# Now_Communicator_Apr_17_2026.net
KiCad netlist of a schematic drawn in EasyEDA
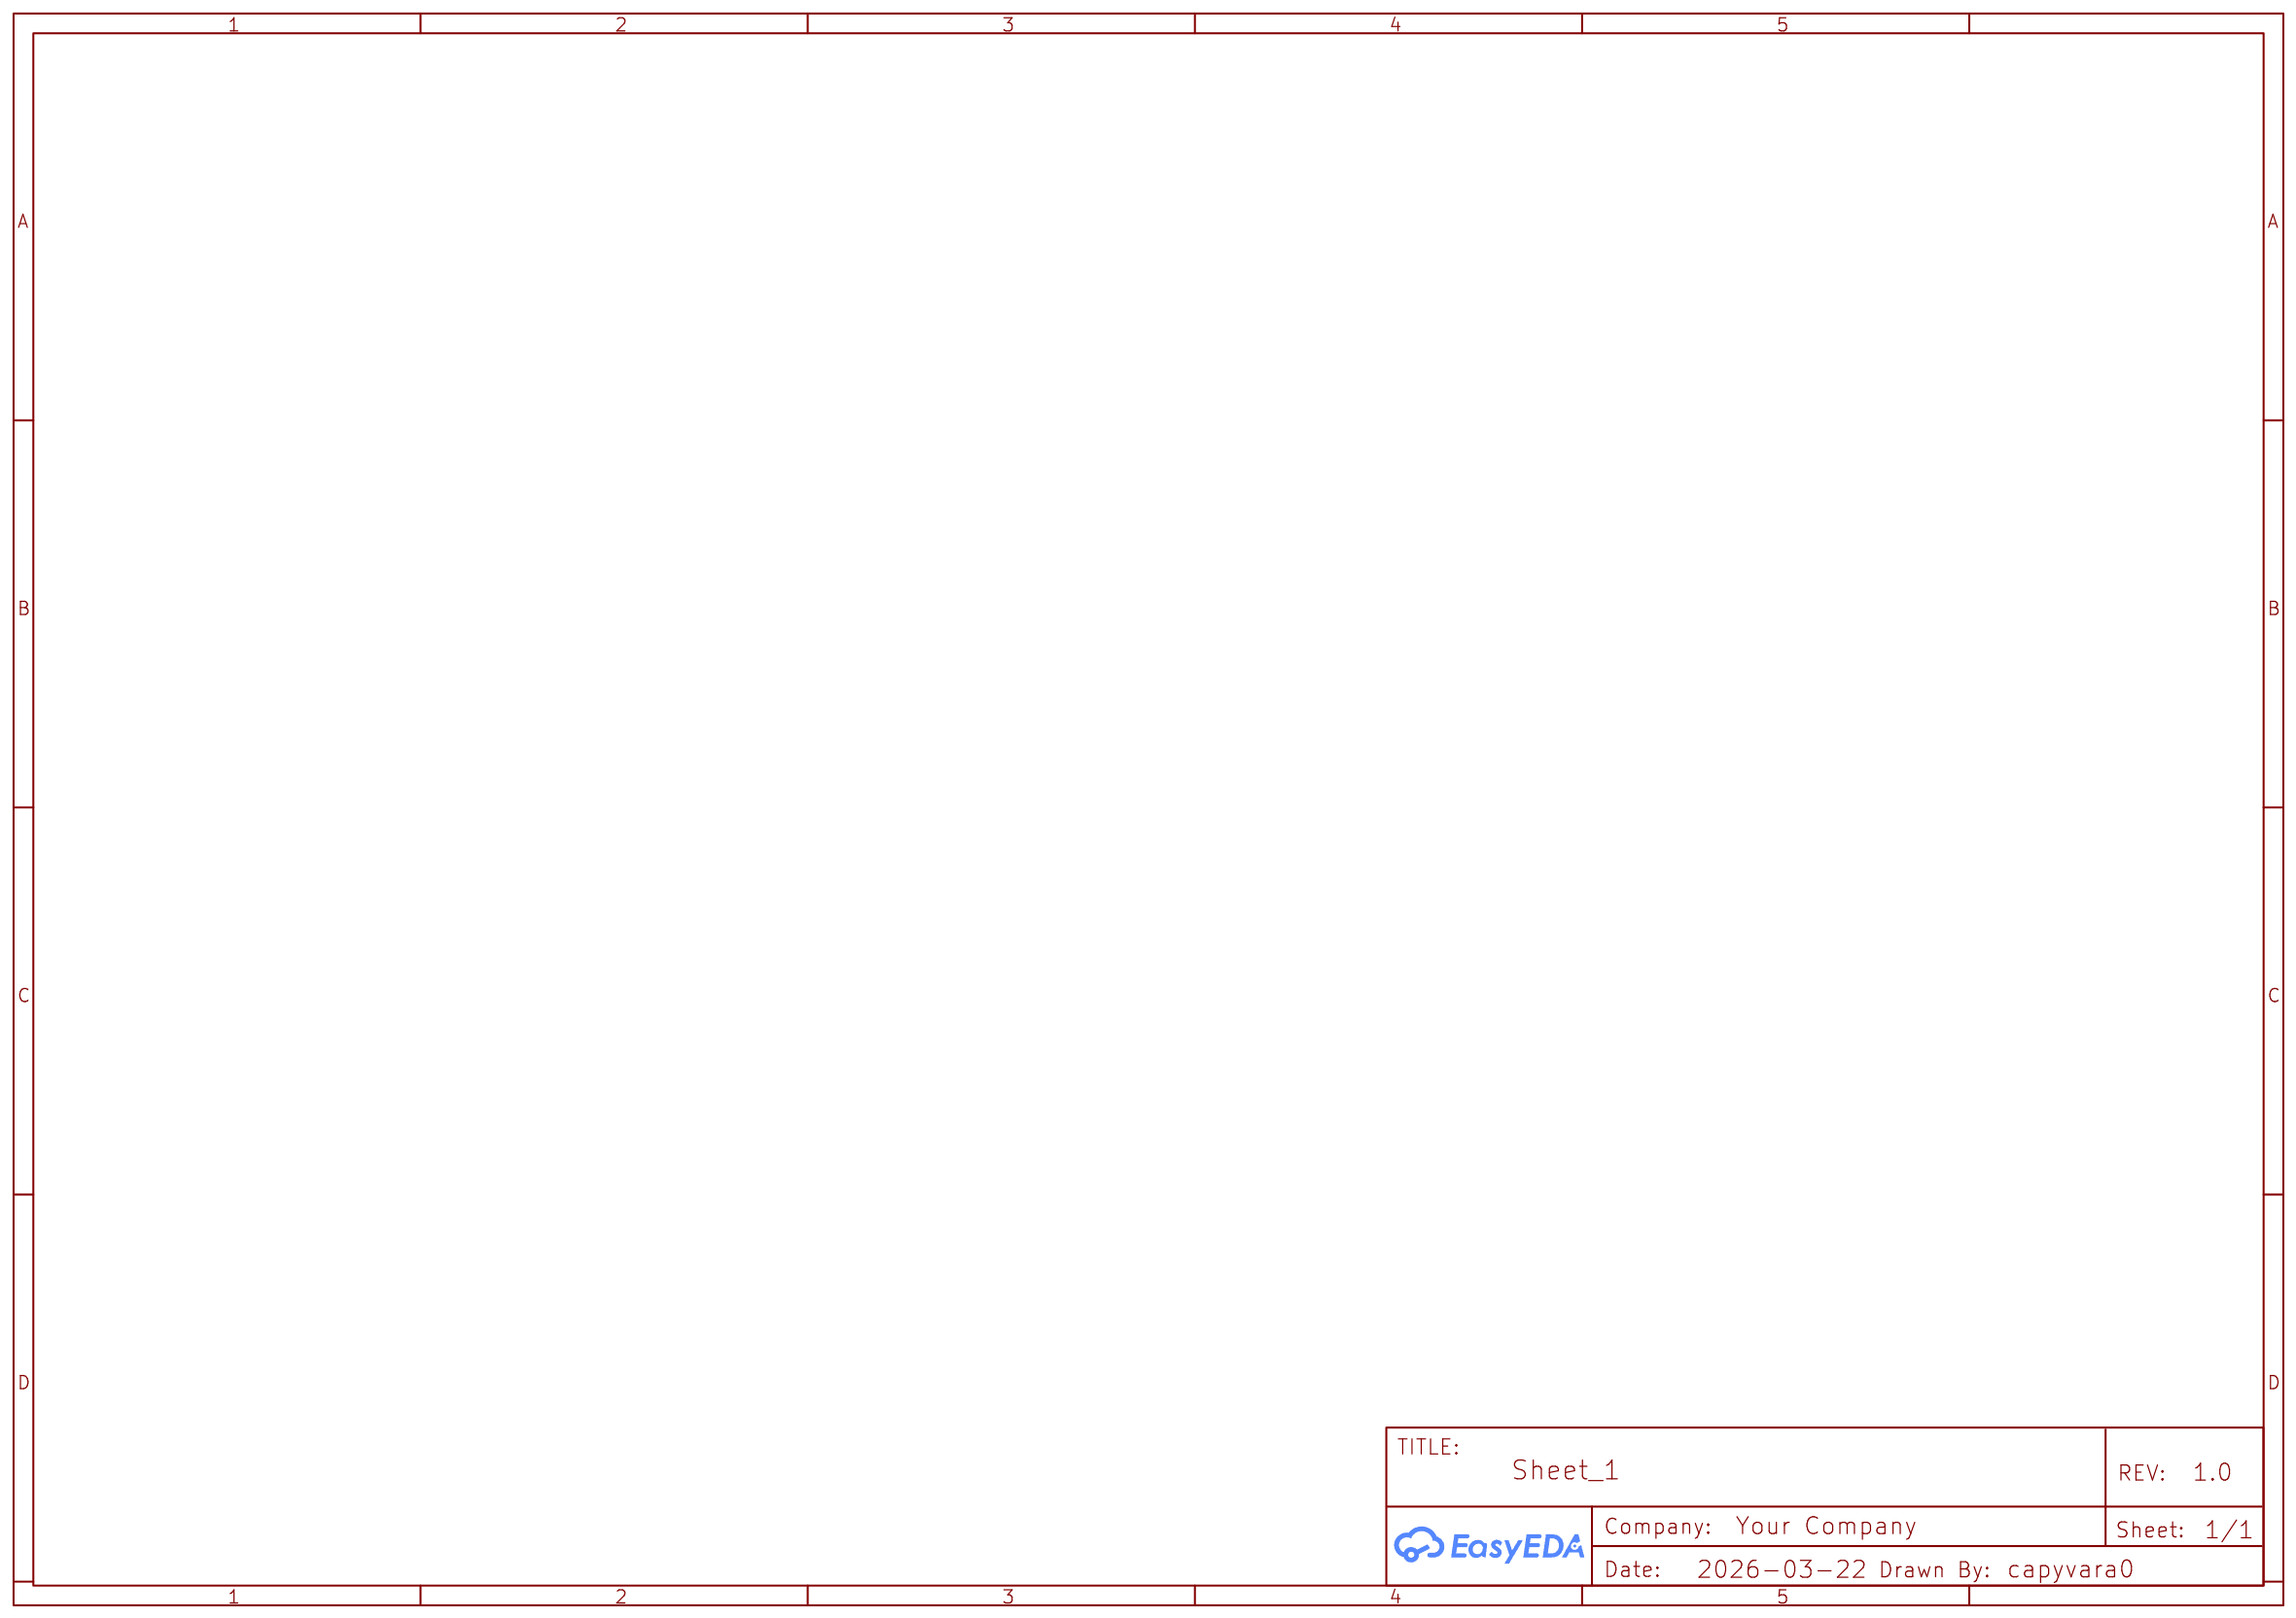
[diagram p0: Sheet_1]
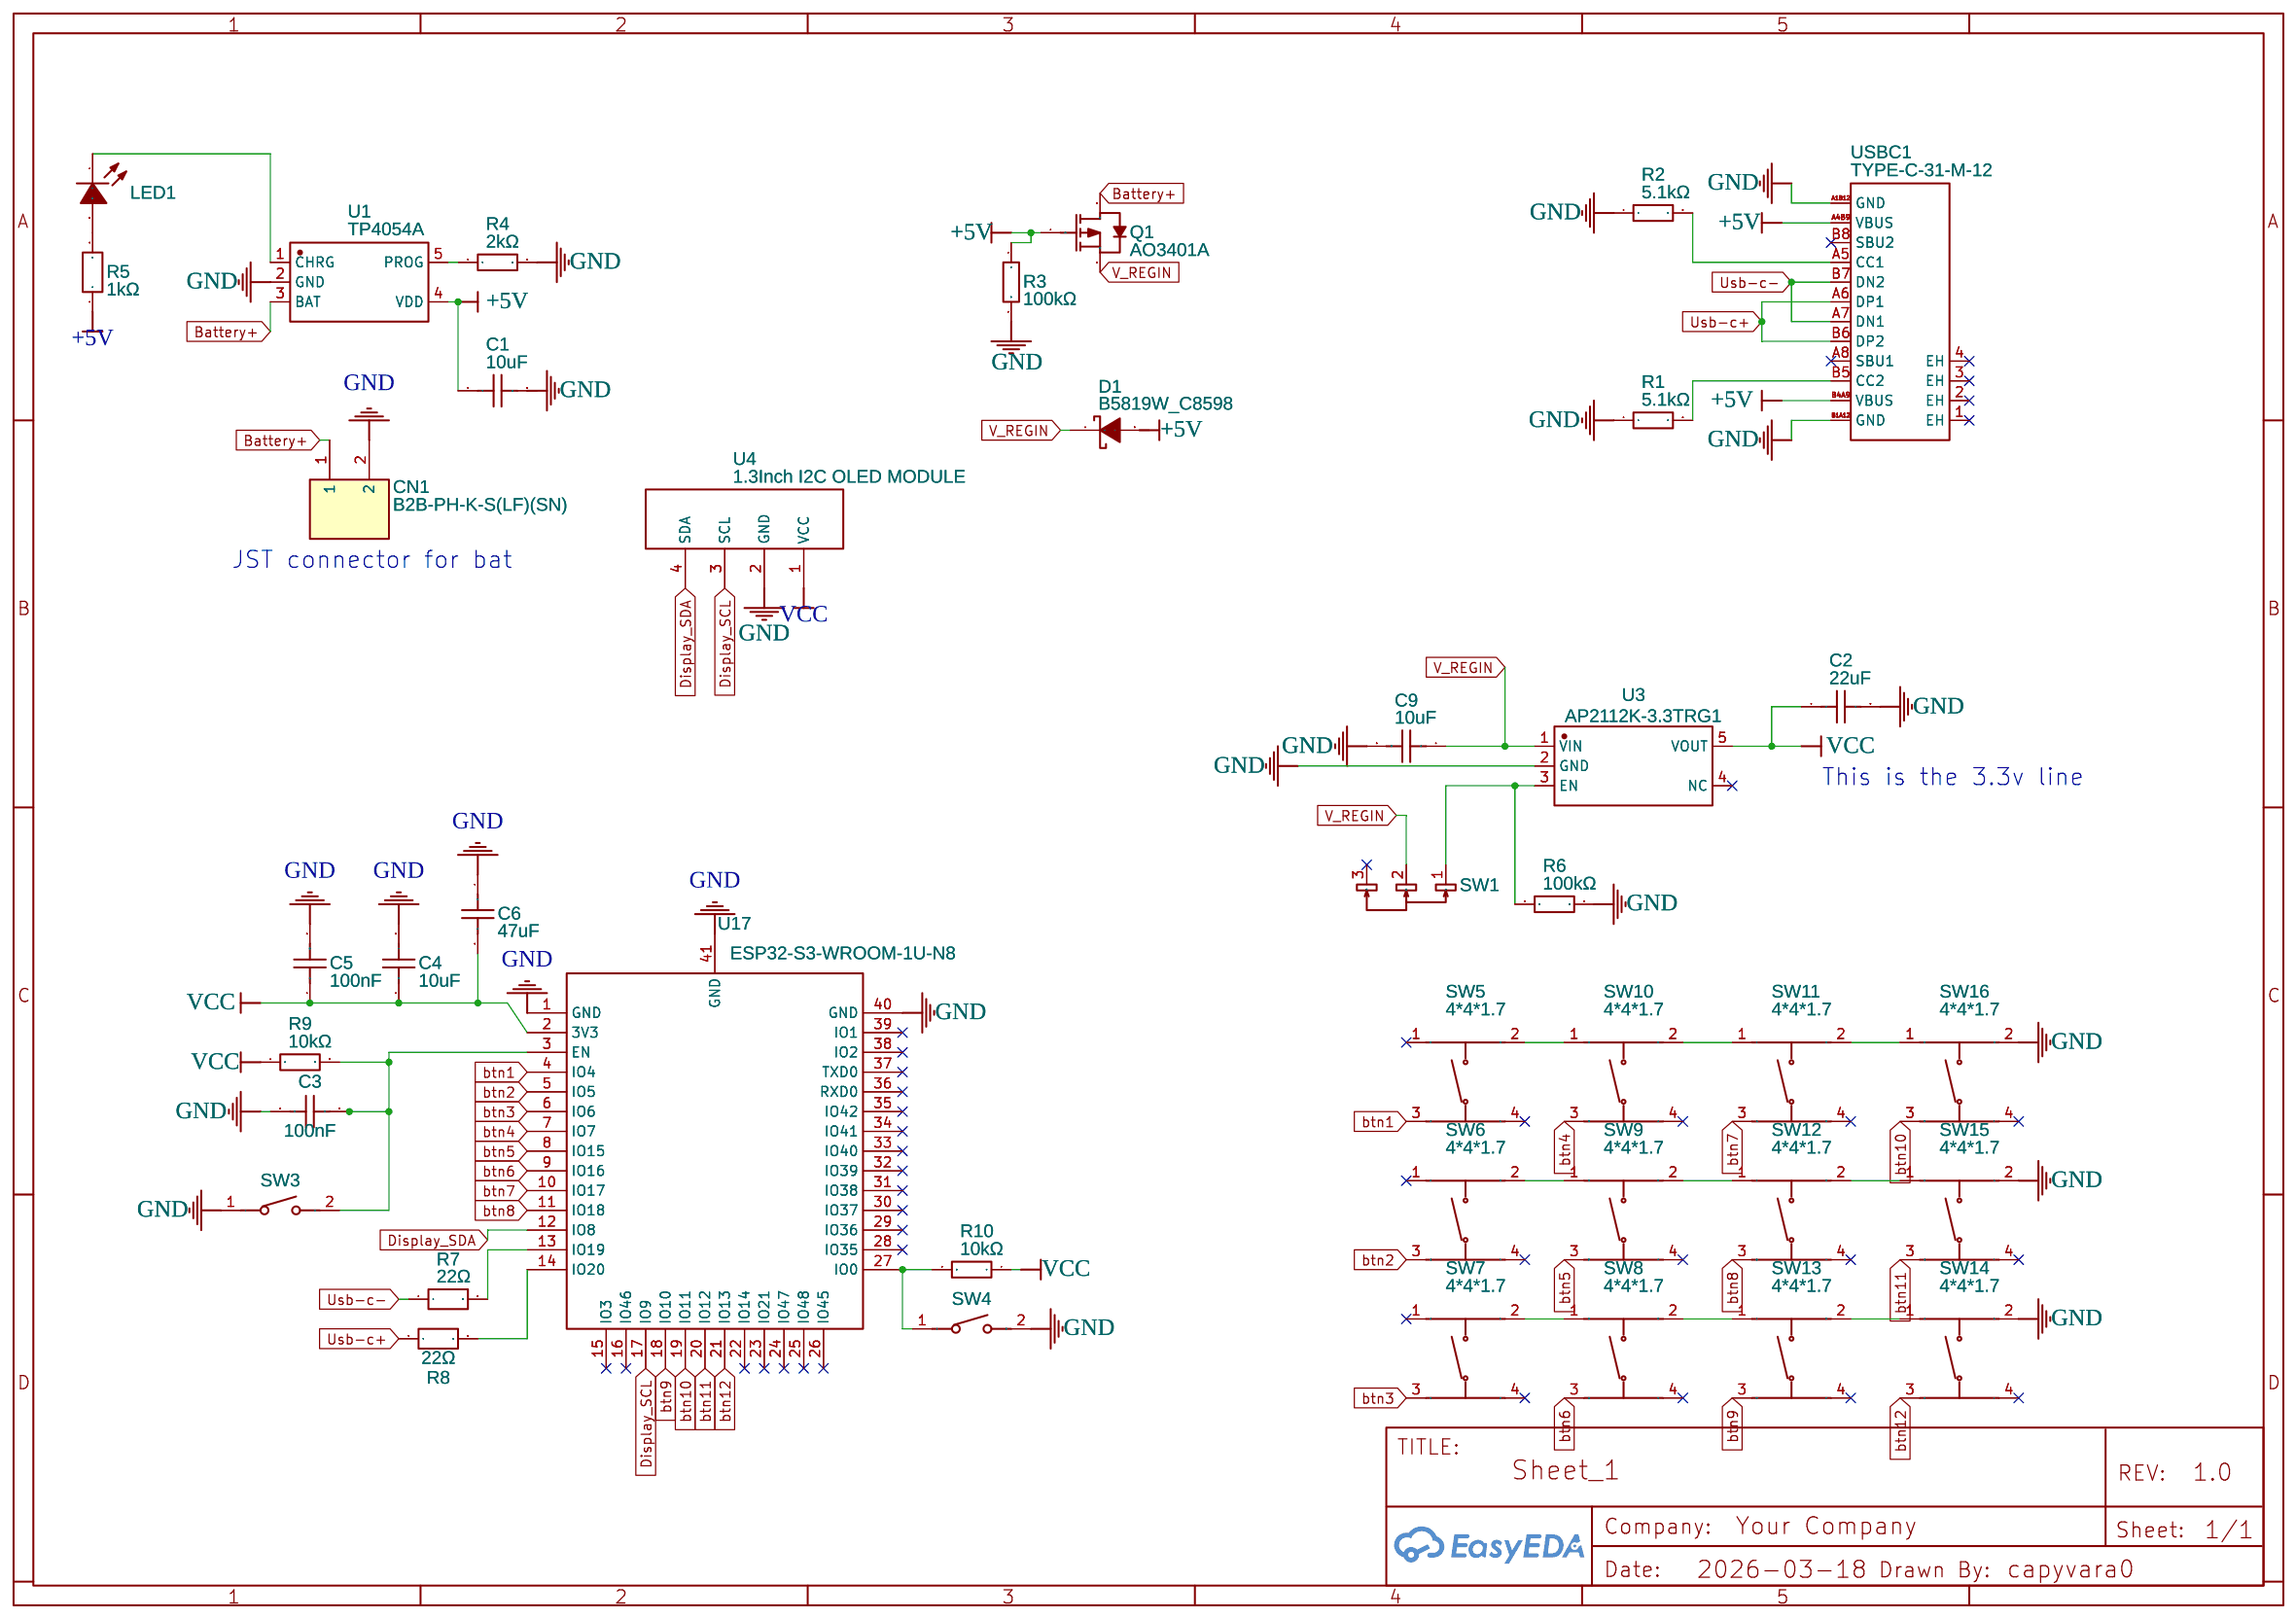
[diagram p1: Sheet_3]

(export (version "E")
  (design (tool "Eeschema 10.0.6"))
  (components
    (comp (ref "C1")
      (value "10uF")
      (fields
        (field (name "Manufacturer Part") "CL10A106KP8NNNC")
        (field (name "Manufacturer") "SAMSUNG(三星)")
      )
      (libsource (lib "") (part "CL10A106KP8NNNC"))
    )
    (comp (ref "C2")
      (value "22uF")
      (fields
        (field (name "Manufacturer Part") "CL10A226MQ8NRNC")
        (field (name "Manufacturer") "SAMSUNG(三星)")
      )
      (libsource (lib "") (part "CL10A226MQ8NRNC"))
    )
    (comp (ref "C3")
      (value "100nF")
      (fields
        (field (name "Manufacturer Part") "VJ0603Y104JXQCW1BC")
        (field (name "Manufacturer") "VISHAY(威世)")
      )
      (libsource (lib "") (part "VJ0603Y104JXQCW1BC"))
    )
    (comp (ref "C4")
      (value "10uF")
      (fields
        (field (name "Manufacturer Part") "CL21A106KAYNNNE")
        (field (name "Manufacturer") "SAMSUNG(三星)")
      )
      (libsource (lib "") (part "CL21A106KAYNNNE"))
    )
    (comp (ref "C5")
      (value "100nF")
      (fields
        (field (name "Manufacturer Part") "CC0805KRX7R9BB104")
        (field (name "Manufacturer") "YAGEO(国巨)")
      )
      (libsource (lib "") (part "CC0805KRX7R9BB104"))
    )
    (comp (ref "C6")
      (value "47uF")
      (fields
        (field (name "Manufacturer Part") "C0805X5R476M100NT")
        (field (name "Manufacturer") "SANYEAR(叁叶源)")
      )
      (libsource (lib "") (part "C0805X5R476M100NT"))
    )
    (comp (ref "C9")
      (value "10uF")
      (fields
        (field (name "Manufacturer Part") "CL10A106KP8NNNC")
        (field (name "Manufacturer") "SAMSUNG(三星)")
      )
      (libsource (lib "") (part "CL10A106KP8NNNC_1"))
    )
    (comp (ref "CN1")
      (value "B2B-PH-K-S(LF)(SN)")
      (fields (field (name "Manufacturer") "JST"))
      (libsource (lib "") (part "B2B-PH-K-S(LF)(SN)"))
    )
    (comp (ref "D1")
      (value "B5819W_C8598")
      (fields (field (name "Manufacturer Part") "B5819W SL") (field (name "Manufacturer") "CJ(江苏长电/长晶)"))
      (libsource (lib "") (part "B5819W_C8598"))
    )
    (comp (ref "LED1")
      (value "FC-2012HRK-620D")
      (fields (field (name "Manufacturer Part") "NCD0805R1") (field (name "Manufacturer") "国星光电"))
      (libsource (lib "") (part "FC-2012HRK-620D"))
    )
    (comp (ref "Q1")
      (value "AO3401A")
      (fields (field (name "Manufacturer") "AOS"))
      (libsource (lib "") (part "AO3401A"))
    )
    (comp (ref "R1")
      (value "5.1kΩ")
      (fields
        (field (name "Manufacturer Part") "0603WAF5101T5E")
        (field (name "Manufacturer") "UNI-ROYAL(厚声)")
      )
      (libsource (lib "") (part "0603WAF5101T5E"))
    )
    (comp (ref "R2")
      (value "5.1kΩ")
      (fields
        (field (name "Manufacturer Part") "0603WAF5101T5E")
        (field (name "Manufacturer") "UNI-ROYAL(厚声)")
      )
      (libsource (lib "") (part "0603WAF5101T5E"))
    )
    (comp (ref "R3")
      (value "100kΩ")
      (fields
        (field (name "Manufacturer Part") "0603WAF1003T5E")
        (field (name "Manufacturer") "UNI-ROYAL(厚声)")
      )
      (libsource (lib "") (part "0603WAF1003T5E"))
    )
    (comp (ref "R4")
      (value "2kΩ")
      (fields
        (field (name "Manufacturer Part") "0603WAF2001T5E")
        (field (name "Manufacturer") "UNI-ROYAL(厚声)")
      )
      (libsource (lib "") (part "0603WAF2001T5E"))
    )
    (comp (ref "R5")
      (value "1kΩ")
      (fields (field (name "Manufacturer Part") "FRR0805J102 TS") (field (name "Manufacturer") "FOJAN(富捷)"))
      (libsource (lib "") (part "FRR0805J102 TS"))
    )
    (comp (ref "R6")
      (value "100kΩ")
      (fields
        (field (name "Manufacturer Part") "0805W8F1003T5E")
        (field (name "Manufacturer") "UNI-ROYAL(厚声)")
      )
      (libsource (lib "") (part "0805W8F1003T5E_C149504"))
    )
    (comp (ref "R7")
      (value "22Ω")
      (fields (field (name "Manufacturer Part") "FRC0603F22R0TS") (field (name "Manufacturer") "FOJAN(富捷)"))
      (libsource (lib "") (part "FRC0603F22R0TS"))
    )
    (comp (ref "R8")
      (value "22Ω")
      (fields (field (name "Manufacturer Part") "FRC0603F22R0TS") (field (name "Manufacturer") "FOJAN(富捷)"))
      (libsource (lib "") (part "FRC0603F22R0TS"))
    )
    (comp (ref "R9")
      (value "10kΩ")
      (fields
        (field (name "Manufacturer Part") "0603WAF1002T5E")
        (field (name "Manufacturer") "UNI-ROYAL(厚声)")
      )
      (libsource (lib "") (part "0603WAF1002T5E"))
    )
    (comp (ref "R10")
      (value "10kΩ")
      (fields
        (field (name "Manufacturer Part") "0603WAF1002T5E")
        (field (name "Manufacturer") "UNI-ROYAL(厚声)")
      )
      (libsource (lib "") (part "0603WAF1002T5E_1"))
    )
    (comp (ref "SW1")
      (value "MST-12D18G4 SPDT SLIDE SWITCH")
      (fields
        (field (name "Manufacturer Part") "MST-12D18G4 SPDT Slide Switch")
        (field (name "Manufacturer") "SHOU HAN(首韩)")
      )
      (libsource (lib "") (part "MST-12D18G4 SPDT SLIDE SWITCH"))
    )
    (comp (ref "SW3")
      (value "TS-1088-AR02016")
      (fields (field (name "Manufacturer") "XUNPU(讯普)"))
      (libsource (lib "") (part "TS-1088-AR02016"))
    )
    (comp (ref "SW4")
      (value "TS-1088-AR02016")
      (fields (field (name "Manufacturer") "XUNPU(讯普)"))
      (libsource (lib "") (part "TS-1088-AR02016"))
    )
    (comp (ref "SW5")
      (value "4*4*1.7")
      (fields (field (name "Manufacturer Part") "4*4*1.7 贴片") (field (name "Manufacturer") "BOOMELE(博穆精密)"))
      (libsource (lib "") (part "4*4*1.7"))
    )
    (comp (ref "SW6")
      (value "4*4*1.7")
      (fields (field (name "Manufacturer Part") "4*4*1.7 贴片") (field (name "Manufacturer") "BOOMELE(博穆精密)"))
      (libsource (lib "") (part "4*4*1.7"))
    )
    (comp (ref "SW7")
      (value "4*4*1.7")
      (fields (field (name "Manufacturer Part") "4*4*1.7 贴片") (field (name "Manufacturer") "BOOMELE(博穆精密)"))
      (libsource (lib "") (part "4*4*1.7"))
    )
    (comp (ref "SW8")
      (value "4*4*1.7")
      (fields (field (name "Manufacturer Part") "4*4*1.7 贴片") (field (name "Manufacturer") "BOOMELE(博穆精密)"))
      (libsource (lib "") (part "4*4*1.7"))
    )
    (comp (ref "SW9")
      (value "4*4*1.7")
      (fields (field (name "Manufacturer Part") "4*4*1.7 贴片") (field (name "Manufacturer") "BOOMELE(博穆精密)"))
      (libsource (lib "") (part "4*4*1.7"))
    )
    (comp (ref "SW10")
      (value "4*4*1.7")
      (fields (field (name "Manufacturer Part") "4*4*1.7 贴片") (field (name "Manufacturer") "BOOMELE(博穆精密)"))
      (libsource (lib "") (part "4*4*1.7"))
    )
    (comp (ref "SW11")
      (value "4*4*1.7")
      (fields (field (name "Manufacturer Part") "4*4*1.7 贴片") (field (name "Manufacturer") "BOOMELE(博穆精密)"))
      (libsource (lib "") (part "4*4*1.7"))
    )
    (comp (ref "SW12")
      (value "4*4*1.7")
      (fields (field (name "Manufacturer Part") "4*4*1.7 贴片") (field (name "Manufacturer") "BOOMELE(博穆精密)"))
      (libsource (lib "") (part "4*4*1.7"))
    )
    (comp (ref "SW13")
      (value "4*4*1.7")
      (fields (field (name "Manufacturer Part") "4*4*1.7 贴片") (field (name "Manufacturer") "BOOMELE(博穆精密)"))
      (libsource (lib "") (part "4*4*1.7"))
    )
    (comp (ref "SW14")
      (value "4*4*1.7")
      (fields (field (name "Manufacturer Part") "4*4*1.7 贴片") (field (name "Manufacturer") "BOOMELE(博穆精密)"))
      (libsource (lib "") (part "4*4*1.7"))
    )
    (comp (ref "SW15")
      (value "4*4*1.7")
      (fields (field (name "Manufacturer Part") "4*4*1.7 贴片") (field (name "Manufacturer") "BOOMELE(博穆精密)"))
      (libsource (lib "") (part "4*4*1.7"))
    )
    (comp (ref "SW16")
      (value "4*4*1.7")
      (fields (field (name "Manufacturer Part") "4*4*1.7 贴片") (field (name "Manufacturer") "BOOMELE(博穆精密)"))
      (libsource (lib "") (part "4*4*1.7"))
    )
    (comp (ref "U1")
      (value "TP4054A")
      (fields (field (name "Manufacturer") "YONGYUTAI(永裕泰)"))
      (libsource (lib "") (part "TP4054A"))
    )
    (comp (ref "U3")
      (value "AP2112K-3.3TRG1")
      (fields (field (name "Manufacturer") "DIODES(美台)"))
      (libsource (lib "") (part "AP2112K-3.3TRG1"))
    )
    (comp (ref "U4") (value "1.3Inch I2C OLED MODULE") (libsource (lib "") (part "1.3Inch I2C OLED MODULE")))
    (comp (ref "U17")
      (value "ESP32-S3-WROOM-1U-N8")
      (fields (field (name "Manufacturer") "ESPRESSIF(乐鑫)"))
      (libsource (lib "") (part "ESP32-S3-WROOM-1U-N8"))
    )
    (comp (ref "USBC1")
      (value "TYPE-C-31-M-12")
      (fields (field (name "Manufacturer") "韩国韩荣"))
      (libsource (lib "") (part "TYPE-C-31-M-12"))
    )
  )
  (nets
    (net (code "1") (name "+5V") (class "Default")
      (node (ref "C1") (pin "1") (pinfunction "1_1") (pintype "unspecified"))
      (node (ref "D1") (pin "2") (pinfunction "+_2") (pintype "unspecified"))
      (node (ref "Q1") (pin "1") (pinfunction "G_1") (pintype "unspecified"))
      (node (ref "R3") (pin "1") (pinfunction "1_1") (pintype "input"))
      (node (ref "R5") (pin "1") (pinfunction "1_1") (pintype "unspecified"))
      (node (ref "U1") (pin "4") (pinfunction "VDD_4") (pintype "unspecified"))
      (node (ref "USBC1") (pin "A4B9") (pinfunction "VBUS_A4B9") (pintype "unspecified"))
      (node (ref "USBC1") (pin "B4A9") (pinfunction "VBUS_B4A9") (pintype "unspecified"))
    )
    (net (code "2") (name "Battery+") (class "Default")
      (node (ref "CN1") (pin "1") (pinfunction "1_1") (pintype "input"))
      (node (ref "Q1") (pin "3") (pinfunction "D_3") (pintype "unspecified"))
      (node (ref "U1") (pin "3") (pinfunction "BAT_3") (pintype "unspecified"))
    )
    (net (code "3") (name "Display_SCL") (class "Default")
      (node (ref "U17") (pin "17") (pinfunction "IO9_17") (pintype "unspecified"))
      (node (ref "U4") (pin "3") (pinfunction "SCL_3") (pintype "unspecified"))
    )
    (net (code "4") (name "Display_SDA") (class "Default")
      (node (ref "U17") (pin "12") (pinfunction "IO8_12") (pintype "unspecified"))
      (node (ref "U4") (pin "4") (pinfunction "SDA_4") (pintype "unspecified"))
    )
    (net (code "5") (name "GND") (class "Default")
      (node (ref "C1") (pin "2") (pinfunction "2_2") (pintype "unspecified"))
      (node (ref "C2") (pin "2") (pinfunction "2_2") (pintype "unspecified"))
      (node (ref "C3") (pin "1") (pinfunction "1_1") (pintype "unspecified"))
      (node (ref "C4") (pin "2") (pinfunction "2_2") (pintype "unspecified"))
      (node (ref "C5") (pin "2") (pinfunction "2_2") (pintype "unspecified"))
      (node (ref "C6") (pin "1") (pinfunction "1_1") (pintype "unspecified"))
      (node (ref "C9") (pin "2") (pinfunction "2_2") (pintype "unspecified"))
      (node (ref "CN1") (pin "2") (pinfunction "2_2") (pintype "input"))
      (node (ref "R1") (pin "1") (pinfunction "1_1") (pintype "input"))
      (node (ref "R2") (pin "1") (pinfunction "1_1") (pintype "input"))
      (node (ref "R3") (pin "2") (pinfunction "2_2") (pintype "input"))
      (node (ref "R4") (pin "2") (pinfunction "2_2") (pintype "input"))
      (node (ref "R6") (pin "2") (pinfunction "2_2") (pintype "unspecified"))
      (node (ref "SW14") (pin "2") (pinfunction "2_2") (pintype "unspecified"))
      (node (ref "SW15") (pin "2") (pinfunction "2_2") (pintype "unspecified"))
      (node (ref "SW16") (pin "2") (pinfunction "2_2") (pintype "unspecified"))
      (node (ref "SW3") (pin "1") (pinfunction "1_1") (pintype "unspecified"))
      (node (ref "SW4") (pin "2") (pinfunction "2_2") (pintype "unspecified"))
      (node (ref "U1") (pin "2") (pinfunction "GND_2") (pintype "unspecified"))
      (node (ref "U17") (pin "1") (pinfunction "GND_1") (pintype "passive"))
      (node (ref "U17") (pin "40") (pinfunction "GND_40") (pintype "passive"))
      (node (ref "U17") (pin "41") (pinfunction "GND_41") (pintype "passive"))
      (node (ref "U3") (pin "2") (pinfunction "GND_2") (pintype "unspecified"))
      (node (ref "U4") (pin "2") (pinfunction "GND_2") (pintype "unspecified"))
      (node (ref "USBC1") (pin "A1B12") (pinfunction "GND_A1B12") (pintype "unspecified"))
      (node (ref "USBC1") (pin "B1A12") (pinfunction "GND_B1A12") (pintype "unspecified"))
    )
    (net (code "6") (name "Net-(LED1-+)") (class "Default")
      (node (ref "LED1") (pin "2") (pinfunction "+_2") (pintype "unspecified"))
      (node (ref "R5") (pin "2") (pinfunction "2_2") (pintype "unspecified"))
    )
    (net (code "7") (name "Net-(LED1--)") (class "Default")
      (node (ref "LED1") (pin "1") (pinfunction "-_1") (pintype "unspecified"))
      (node (ref "U1") (pin "1") (pinfunction "CHRG_1") (pintype "unspecified"))
    )
    (net (code "8") (name "Net-(SW6-Pad2)") (class "Default")
      (node (ref "SW6") (pin "2") (pinfunction "2_2") (pintype "unspecified"))
      (node (ref "SW9") (pin "1") (pinfunction "1_1") (pintype "unspecified"))
    )
    (net (code "9") (name "Net-(SW7-Pad2)") (class "Default")
      (node (ref "SW7") (pin "2") (pinfunction "2_2") (pintype "unspecified"))
      (node (ref "SW8") (pin "1") (pinfunction "1_1") (pintype "unspecified"))
    )
    (net (code "10") (name "Net-(SW10-Pad1)") (class "Default")
      (node (ref "SW10") (pin "1") (pinfunction "1_1") (pintype "unspecified"))
      (node (ref "SW5") (pin "2") (pinfunction "2_2") (pintype "unspecified"))
    )
    (net (code "11") (name "Net-(SW10-Pad2)") (class "Default")
      (node (ref "SW10") (pin "2") (pinfunction "2_2") (pintype "unspecified"))
      (node (ref "SW11") (pin "1") (pinfunction "1_1") (pintype "unspecified"))
    )
    (net (code "12") (name "Net-(SW11-Pad2)") (class "Default")
      (node (ref "SW11") (pin "2") (pinfunction "2_2") (pintype "unspecified"))
      (node (ref "SW16") (pin "1") (pinfunction "1_1") (pintype "unspecified"))
    )
    (net (code "13") (name "Net-(SW12-Pad1)") (class "Default")
      (node (ref "SW12") (pin "1") (pinfunction "1_1") (pintype "unspecified"))
      (node (ref "SW9") (pin "2") (pinfunction "2_2") (pintype "unspecified"))
    )
    (net (code "14") (name "Net-(SW12-Pad2)") (class "Default")
      (node (ref "SW12") (pin "2") (pinfunction "2_2") (pintype "unspecified"))
      (node (ref "SW15") (pin "1") (pinfunction "1_1") (pintype "unspecified"))
    )
    (net (code "15") (name "Net-(SW13-Pad1)") (class "Default")
      (node (ref "SW13") (pin "1") (pinfunction "1_1") (pintype "unspecified"))
      (node (ref "SW8") (pin "2") (pinfunction "2_2") (pintype "unspecified"))
    )
    (net (code "16") (name "Net-(SW13-Pad2)") (class "Default")
      (node (ref "SW13") (pin "2") (pinfunction "2_2") (pintype "unspecified"))
      (node (ref "SW14") (pin "1") (pinfunction "1_1") (pintype "unspecified"))
    )
    (net (code "17") (name "Net-(U1-PROG)") (class "Default")
      (node (ref "R4") (pin "1") (pinfunction "1_1") (pintype "input"))
      (node (ref "U1") (pin "5") (pinfunction "PROG_5") (pintype "unspecified"))
    )
    (net (code "18") (name "Net-(U3-EN)") (class "Default")
      (node (ref "R6") (pin "1") (pinfunction "1_1") (pintype "unspecified"))
      (node (ref "SW1") (pin "1") (pinfunction "1_1") (pintype "unspecified"))
      (node (ref "U3") (pin "3") (pinfunction "EN_3") (pintype "unspecified"))
    )
    (net (code "19") (name "Net-(U17-EN)") (class "Default")
      (node (ref "C3") (pin "2") (pinfunction "2_2") (pintype "unspecified"))
      (node (ref "R9") (pin "2") (pinfunction "2_2") (pintype "input"))
      (node (ref "SW3") (pin "2") (pinfunction "2_2") (pintype "unspecified"))
      (node (ref "U17") (pin "3") (pinfunction "EN_3") (pintype "unspecified"))
    )
    (net (code "20") (name "Net-(U17-IO0)") (class "Default")
      (node (ref "R10") (pin "2") (pinfunction "2_2") (pintype "input"))
      (node (ref "SW4") (pin "1") (pinfunction "1_1") (pintype "unspecified"))
      (node (ref "U17") (pin "27") (pinfunction "IO0_27") (pintype "unspecified"))
    )
    (net (code "21") (name "Net-(U17-IO19)") (class "Default")
      (node (ref "R7") (pin "2") (pinfunction "2_2") (pintype "unspecified"))
      (node (ref "U17") (pin "13") (pinfunction "IO19_13") (pintype "unspecified"))
    )
    (net (code "22") (name "Net-(U17-IO20)") (class "Default")
      (node (ref "R8") (pin "2") (pinfunction "2_2") (pintype "unspecified"))
      (node (ref "U17") (pin "14") (pinfunction "IO20_14") (pintype "unspecified"))
    )
    (net (code "23") (name "Net-(USBC1-CC1)") (class "Default")
      (node (ref "R2") (pin "2") (pinfunction "2_2") (pintype "input"))
      (node (ref "USBC1") (pin "A5") (pinfunction "CC1_A5") (pintype "unspecified"))
    )
    (net (code "24") (name "Net-(USBC1-CC2)") (class "Default")
      (node (ref "R1") (pin "2") (pinfunction "2_2") (pintype "input"))
      (node (ref "USBC1") (pin "B5") (pinfunction "CC2_B5") (pintype "unspecified"))
    )
    (net (code "25") (name "Usb-c+") (class "Default")
      (node (ref "R8") (pin "1") (pinfunction "1_1") (pintype "unspecified"))
      (node (ref "USBC1") (pin "A6") (pinfunction "DP1_A6") (pintype "unspecified"))
      (node (ref "USBC1") (pin "B6") (pinfunction "DP2_B6") (pintype "unspecified"))
    )
    (net (code "26") (name "Usb-c-") (class "Default")
      (node (ref "R7") (pin "1") (pinfunction "1_1") (pintype "unspecified"))
      (node (ref "USBC1") (pin "A7") (pinfunction "DN1_A7") (pintype "unspecified"))
      (node (ref "USBC1") (pin "B7") (pinfunction "DN2_B7") (pintype "unspecified"))
    )
    (net (code "27") (name "VCC") (class "Default")
      (node (ref "C2") (pin "1") (pinfunction "1_1") (pintype "unspecified"))
      (node (ref "C4") (pin "1") (pinfunction "1_1") (pintype "unspecified"))
      (node (ref "C5") (pin "1") (pinfunction "1_1") (pintype "unspecified"))
      (node (ref "C6") (pin "2") (pinfunction "2_2") (pintype "unspecified"))
      (node (ref "R10") (pin "1") (pinfunction "1_1") (pintype "input"))
      (node (ref "R9") (pin "1") (pinfunction "1_1") (pintype "input"))
      (node (ref "U17") (pin "2") (pinfunction "3V3_2") (pintype "passive"))
      (node (ref "U3") (pin "5") (pinfunction "VOUT_5") (pintype "unspecified"))
      (node (ref "U4") (pin "1") (pinfunction "VCC_1") (pintype "unspecified"))
    )
    (net (code "28") (name "V_REGIN") (class "Default")
      (node (ref "C9") (pin "1") (pinfunction "1_1") (pintype "unspecified"))
      (node (ref "D1") (pin "1") (pinfunction "-_1") (pintype "unspecified"))
      (node (ref "Q1") (pin "2") (pinfunction "S_2") (pintype "unspecified"))
      (node (ref "SW1") (pin "2") (pinfunction "2_2") (pintype "unspecified"))
      (node (ref "U3") (pin "1") (pinfunction "VIN_1") (pintype "unspecified"))
    )
    (net (code "29") (name "btn1") (class "Default")
      (node (ref "SW5") (pin "3") (pinfunction "3_3") (pintype "unspecified"))
      (node (ref "U17") (pin "4") (pinfunction "IO4_4") (pintype "unspecified"))
    )
    (net (code "30") (name "btn2") (class "Default")
      (node (ref "SW6") (pin "3") (pinfunction "3_3") (pintype "unspecified"))
      (node (ref "U17") (pin "5") (pinfunction "IO5_5") (pintype "unspecified"))
    )
    (net (code "31") (name "btn3") (class "Default")
      (node (ref "SW7") (pin "3") (pinfunction "3_3") (pintype "unspecified"))
      (node (ref "U17") (pin "6") (pinfunction "IO6_6") (pintype "unspecified"))
    )
    (net (code "32") (name "btn4") (class "Default")
      (node (ref "SW10") (pin "3") (pinfunction "3_3") (pintype "unspecified"))
      (node (ref "U17") (pin "7") (pinfunction "IO7_7") (pintype "unspecified"))
    )
    (net (code "33") (name "btn5") (class "Default")
      (node (ref "SW9") (pin "3") (pinfunction "3_3") (pintype "unspecified"))
      (node (ref "U17") (pin "8") (pinfunction "IO15_8") (pintype "unspecified"))
    )
    (net (code "34") (name "btn6") (class "Default")
      (node (ref "SW8") (pin "3") (pinfunction "3_3") (pintype "unspecified"))
      (node (ref "U17") (pin "9") (pinfunction "IO16_9") (pintype "unspecified"))
    )
    (net (code "35") (name "btn7") (class "Default")
      (node (ref "SW11") (pin "3") (pinfunction "3_3") (pintype "unspecified"))
      (node (ref "U17") (pin "10") (pinfunction "IO17_10") (pintype "unspecified"))
    )
    (net (code "36") (name "btn8") (class "Default")
      (node (ref "SW12") (pin "3") (pinfunction "3_3") (pintype "unspecified"))
      (node (ref "U17") (pin "11") (pinfunction "IO18_11") (pintype "unspecified"))
    )
    (net (code "37") (name "btn9") (class "Default")
      (node (ref "SW13") (pin "3") (pinfunction "3_3") (pintype "unspecified"))
      (node (ref "U17") (pin "18") (pinfunction "IO10_18") (pintype "unspecified"))
    )
    (net (code "38") (name "btn10") (class "Default")
      (node (ref "SW16") (pin "3") (pinfunction "3_3") (pintype "unspecified"))
      (node (ref "U17") (pin "19") (pinfunction "IO11_19") (pintype "unspecified"))
    )
    (net (code "39") (name "btn11") (class "Default")
      (node (ref "SW15") (pin "3") (pinfunction "3_3") (pintype "unspecified"))
      (node (ref "U17") (pin "20") (pinfunction "IO12_20") (pintype "unspecified"))
    )
    (net (code "40") (name "btn12") (class "Default")
      (node (ref "SW14") (pin "3") (pinfunction "3_3") (pintype "unspecified"))
      (node (ref "U17") (pin "21") (pinfunction "IO13_21") (pintype "unspecified"))
    )
    (net (code "41") (name "unconnected-(SW1-Pad3)") (class "Default")
      (node (ref "SW1") (pin "3") (pinfunction "3_3") (pintype "unspecified+no_connect"))
    )
    (net (code "42") (name "unconnected-(SW5-Pad1)") (class "Default")
      (node (ref "SW5") (pin "1") (pinfunction "1_1") (pintype "unspecified+no_connect"))
    )
    (net (code "43") (name "unconnected-(SW5-Pad4)") (class "Default")
      (node (ref "SW5") (pin "4") (pinfunction "4_4") (pintype "unspecified+no_connect"))
    )
    (net (code "44") (name "unconnected-(SW6-Pad1)") (class "Default")
      (node (ref "SW6") (pin "1") (pinfunction "1_1") (pintype "unspecified+no_connect"))
    )
    (net (code "45") (name "unconnected-(SW6-Pad4)") (class "Default")
      (node (ref "SW6") (pin "4") (pinfunction "4_4") (pintype "unspecified+no_connect"))
    )
    (net (code "46") (name "unconnected-(SW7-Pad1)") (class "Default")
      (node (ref "SW7") (pin "1") (pinfunction "1_1") (pintype "unspecified+no_connect"))
    )
    (net (code "47") (name "unconnected-(SW7-Pad4)") (class "Default")
      (node (ref "SW7") (pin "4") (pinfunction "4_4") (pintype "unspecified+no_connect"))
    )
    (net (code "48") (name "unconnected-(SW8-Pad4)") (class "Default")
      (node (ref "SW8") (pin "4") (pinfunction "4_4") (pintype "unspecified+no_connect"))
    )
    (net (code "49") (name "unconnected-(SW9-Pad4)") (class "Default")
      (node (ref "SW9") (pin "4") (pinfunction "4_4") (pintype "unspecified+no_connect"))
    )
    (net (code "50") (name "unconnected-(SW10-Pad4)") (class "Default")
      (node (ref "SW10") (pin "4") (pinfunction "4_4") (pintype "unspecified+no_connect"))
    )
    (net (code "51") (name "unconnected-(SW11-Pad4)") (class "Default")
      (node (ref "SW11") (pin "4") (pinfunction "4_4") (pintype "unspecified+no_connect"))
    )
    (net (code "52") (name "unconnected-(SW12-Pad4)") (class "Default")
      (node (ref "SW12") (pin "4") (pinfunction "4_4") (pintype "unspecified+no_connect"))
    )
    (net (code "53") (name "unconnected-(SW13-Pad4)") (class "Default")
      (node (ref "SW13") (pin "4") (pinfunction "4_4") (pintype "unspecified+no_connect"))
    )
    (net (code "54") (name "unconnected-(SW14-Pad4)") (class "Default")
      (node (ref "SW14") (pin "4") (pinfunction "4_4") (pintype "unspecified+no_connect"))
    )
    (net (code "55") (name "unconnected-(SW15-Pad4)") (class "Default")
      (node (ref "SW15") (pin "4") (pinfunction "4_4") (pintype "unspecified+no_connect"))
    )
    (net (code "56") (name "unconnected-(SW16-Pad4)") (class "Default")
      (node (ref "SW16") (pin "4") (pinfunction "4_4") (pintype "unspecified+no_connect"))
    )
    (net (code "57") (name "unconnected-(U3-NC-Pad4)") (class "Default")
      (node (ref "U3") (pin "4") (pinfunction "NC_4") (pintype "unspecified+no_connect"))
    )
    (net (code "58") (name "unconnected-(U17-IO1-Pad39)") (class "Default")
      (node (ref "U17") (pin "39") (pinfunction "IO1_39") (pintype "unspecified+no_connect"))
    )
    (net (code "59") (name "unconnected-(U17-IO2-Pad38)") (class "Default")
      (node (ref "U17") (pin "38") (pinfunction "IO2_38") (pintype "unspecified+no_connect"))
    )
    (net (code "60") (name "unconnected-(U17-IO3-Pad15)") (class "Default")
      (node (ref "U17") (pin "15") (pinfunction "IO3_15") (pintype "unspecified+no_connect"))
    )
    (net (code "61") (name "unconnected-(U17-IO14-Pad22)") (class "Default")
      (node (ref "U17") (pin "22") (pinfunction "IO14_22") (pintype "unspecified+no_connect"))
    )
    (net (code "62") (name "unconnected-(U17-IO21-Pad23)") (class "Default")
      (node (ref "U17") (pin "23") (pinfunction "IO21_23") (pintype "unspecified+no_connect"))
    )
    (net (code "63") (name "unconnected-(U17-IO35-Pad28)") (class "Default")
      (node (ref "U17") (pin "28") (pinfunction "IO35_28") (pintype "unspecified+no_connect"))
    )
    (net (code "64") (name "unconnected-(U17-IO36-Pad29)") (class "Default")
      (node (ref "U17") (pin "29") (pinfunction "IO36_29") (pintype "unspecified+no_connect"))
    )
    (net (code "65") (name "unconnected-(U17-IO37-Pad30)") (class "Default")
      (node (ref "U17") (pin "30") (pinfunction "IO37_30") (pintype "unspecified+no_connect"))
    )
    (net (code "66") (name "unconnected-(U17-IO38-Pad31)") (class "Default")
      (node (ref "U17") (pin "31") (pinfunction "IO38_31") (pintype "unspecified+no_connect"))
    )
    (net (code "67") (name "unconnected-(U17-IO39-Pad32)") (class "Default")
      (node (ref "U17") (pin "32") (pinfunction "IO39_32") (pintype "unspecified+no_connect"))
    )
    (net (code "68") (name "unconnected-(U17-IO40-Pad33)") (class "Default")
      (node (ref "U17") (pin "33") (pinfunction "IO40_33") (pintype "unspecified+no_connect"))
    )
    (net (code "69") (name "unconnected-(U17-IO41-Pad34)") (class "Default")
      (node (ref "U17") (pin "34") (pinfunction "IO41_34") (pintype "unspecified+no_connect"))
    )
    (net (code "70") (name "unconnected-(U17-IO42-Pad35)") (class "Default")
      (node (ref "U17") (pin "35") (pinfunction "IO42_35") (pintype "unspecified+no_connect"))
    )
    (net (code "71") (name "unconnected-(U17-IO45-Pad26)") (class "Default")
      (node (ref "U17") (pin "26") (pinfunction "IO45_26") (pintype "unspecified+no_connect"))
    )
    (net (code "72") (name "unconnected-(U17-IO46-Pad16)") (class "Default")
      (node (ref "U17") (pin "16") (pinfunction "IO46_16") (pintype "unspecified+no_connect"))
    )
    (net (code "73") (name "unconnected-(U17-IO47-Pad24)") (class "Default")
      (node (ref "U17") (pin "24") (pinfunction "IO47_24") (pintype "unspecified+no_connect"))
    )
    (net (code "74") (name "unconnected-(U17-IO48-Pad25)") (class "Default")
      (node (ref "U17") (pin "25") (pinfunction "IO48_25") (pintype "unspecified+no_connect"))
    )
    (net (code "75") (name "unconnected-(U17-RXD0-Pad36)") (class "Default")
      (node (ref "U17") (pin "36") (pinfunction "RXD0_36") (pintype "unspecified+no_connect"))
    )
    (net (code "76") (name "unconnected-(U17-TXD0-Pad37)") (class "Default")
      (node (ref "U17") (pin "37") (pinfunction "TXD0_37") (pintype "unspecified+no_connect"))
    )
    (net (code "77") (name "unconnected-(USBC1-EH-Pad1)") (class "Default")
      (node (ref "USBC1") (pin "1") (pinfunction "EH_1") (pintype "unspecified+no_connect"))
    )
    (net (code "78") (name "unconnected-(USBC1-EH-Pad2)") (class "Default")
      (node (ref "USBC1") (pin "2") (pinfunction "EH_2") (pintype "unspecified+no_connect"))
    )
    (net (code "79") (name "unconnected-(USBC1-EH-Pad3)") (class "Default")
      (node (ref "USBC1") (pin "3") (pinfunction "EH_3") (pintype "unspecified+no_connect"))
    )
    (net (code "80") (name "unconnected-(USBC1-EH-Pad4)") (class "Default")
      (node (ref "USBC1") (pin "4") (pinfunction "EH_4") (pintype "unspecified+no_connect"))
    )
    (net (code "81") (name "unconnected-(USBC1-SBU1-PadA8)") (class "Default")
      (node (ref "USBC1") (pin "A8") (pinfunction "SBU1_A8") (pintype "unspecified+no_connect"))
    )
    (net (code "82") (name "unconnected-(USBC1-SBU2-PadB8)") (class "Default")
      (node (ref "USBC1") (pin "B8") (pinfunction "SBU2_B8") (pintype "unspecified+no_connect"))
    )
  )
)
